# rtc.net
KiCad netlist of a schematic drawn in Altium Designer
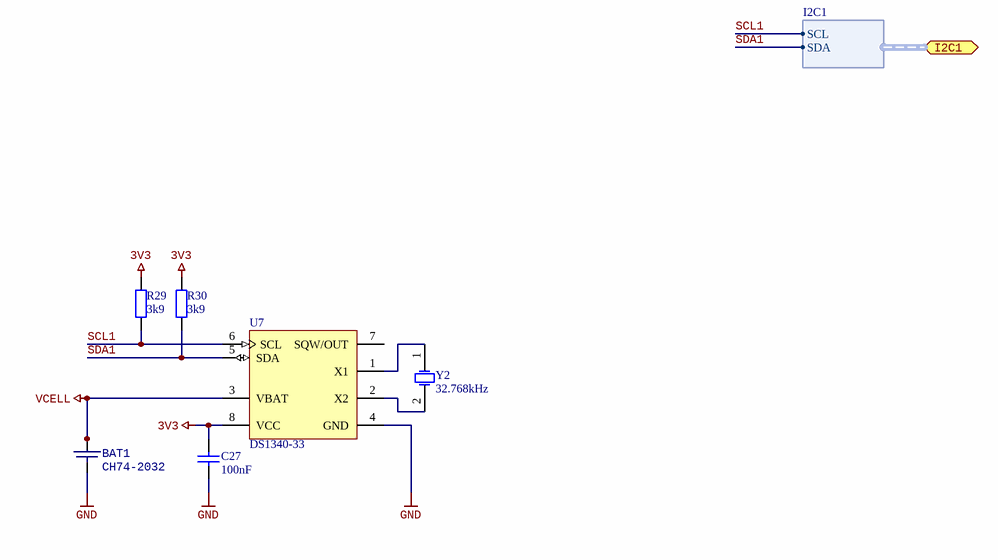
[diagram p0: rtc.SchDoc]

(export (version "E")
  (design (tool "Eeschema 10.0.6"))
  (components
    (comp (ref "BAT1")
      (value "CH74-2032")
      (footprint "BAT_2032_HOLDER")
      (libsource (lib "my_various_devices") (part "CH74-2032"))
    )
    (comp (ref "C27")
      (value "100nF")
      (footprint "CAPC1608N")
      (description "Capacitor")
      (libsource (lib "Discrete") (part "Capacitor"))
    )
    (comp (ref "R29")
      (value "3k9")
      (footprint "Chip_Resistor_N:RESC1608N")
      (description "Resistor")
      (fields (field (name "TOLERANCE") "5%") (field (name "POWER") "0W"))
      (libsource (lib "Discrete") (part "Resistor"))
    )
    (comp (ref "R30")
      (value "3k9")
      (footprint "Chip_Resistor_N:RESC1608N")
      (description "Resistor")
      (fields (field (name "TOLERANCE") "5%") (field (name "POWER") "0W"))
      (libsource (lib "Discrete") (part "Resistor"))
    )
    (comp (ref "U7")
      (value "DS1340-33")
      (footprint "Mechatronic:SO-8_L")
      (description "64 x 8, Serial, I2C Real-Time Clock, 5.0V, 8-Pin SO, -40 to 85 degC, Pb-Free")
      (libsource (lib "Altium Content Vault") (part "PR_RTC_DS1307-IL8"))
    )
    (comp (ref "Y2")
      (value "32.768kHz")
      (footprint "ABS25-crystal")
      (description "Crystal Oscillator")
      (libsource (lib "Discrete") (part "XTAL"))
    )
  )
  (nets
    (net (code "2") (name "/SCL1") (class "Default")
      (node (ref "R29") (pin "2") (pinfunction "2_2") (pintype "passive"))
      (node (ref "U7") (pin "6") (pinfunction "SCL_6") (pintype "input"))
    )
    (net (code "3") (name "/SDA1") (class "Default")
      (node (ref "R30") (pin "2") (pinfunction "2_2") (pintype "passive"))
      (node (ref "U7") (pin "5") (pinfunction "SDA_5") (pintype "bidirectional"))
    )
    (net (code "5") (name "3V3") (class "Default")
      (node (ref "C27") (pin "2") (pinfunction "2_2") (pintype "passive"))
      (node (ref "R29") (pin "1") (pinfunction "1_1") (pintype "passive"))
      (node (ref "R30") (pin "1") (pinfunction "1_1") (pintype "passive"))
      (node (ref "U7") (pin "8") (pinfunction "VCC_8") (pintype "power_in"))
    )
    (net (code "6") (name "GND") (class "Default")
      (node (ref "BAT1") (pin "3") (pinfunction "BAT-_3") (pintype "power_in"))
      (node (ref "C27") (pin "1") (pinfunction "1_1") (pintype "passive"))
      (node (ref "U7") (pin "4") (pinfunction "GND_4") (pintype "power_in"))
    )
    (net (code "7") (name "Net-(U7-X1)") (class "Default")
      (node (ref "U7") (pin "1") (pinfunction "X1_1") (pintype "passive"))
      (node (ref "Y2") (pin "1") (pinfunction "OSC1_1") (pintype "passive"))
    )
    (net (code "8") (name "Net-(U7-X2)") (class "Default")
      (node (ref "U7") (pin "2") (pinfunction "X2_2") (pintype "passive"))
      (node (ref "Y2") (pin "2") (pinfunction "OSC2_2") (pintype "passive"))
    )
    (net (code "9") (name "VCELL") (class "Default")
      (node (ref "BAT1") (pin "1") (pinfunction "BAT+_1") (pintype "power_in"))
      (node (ref "BAT1") (pin "2") (pinfunction "BAT+_2") (pintype "power_in"))
      (node (ref "U7") (pin "3") (pinfunction "VBAT_3") (pintype "power_in"))
    )
    (net (code "10") (name "unconnected-(U7-SQW{slash}OUT-Pad7)") (class "Default")
      (node (ref "U7") (pin "7") (pinfunction "SQW/OUT_7") (pintype "open_collector"))
    )
  )
)
